# Project_Schem_v1.net
KiCad netlist of a schematic drawn in EAGLE
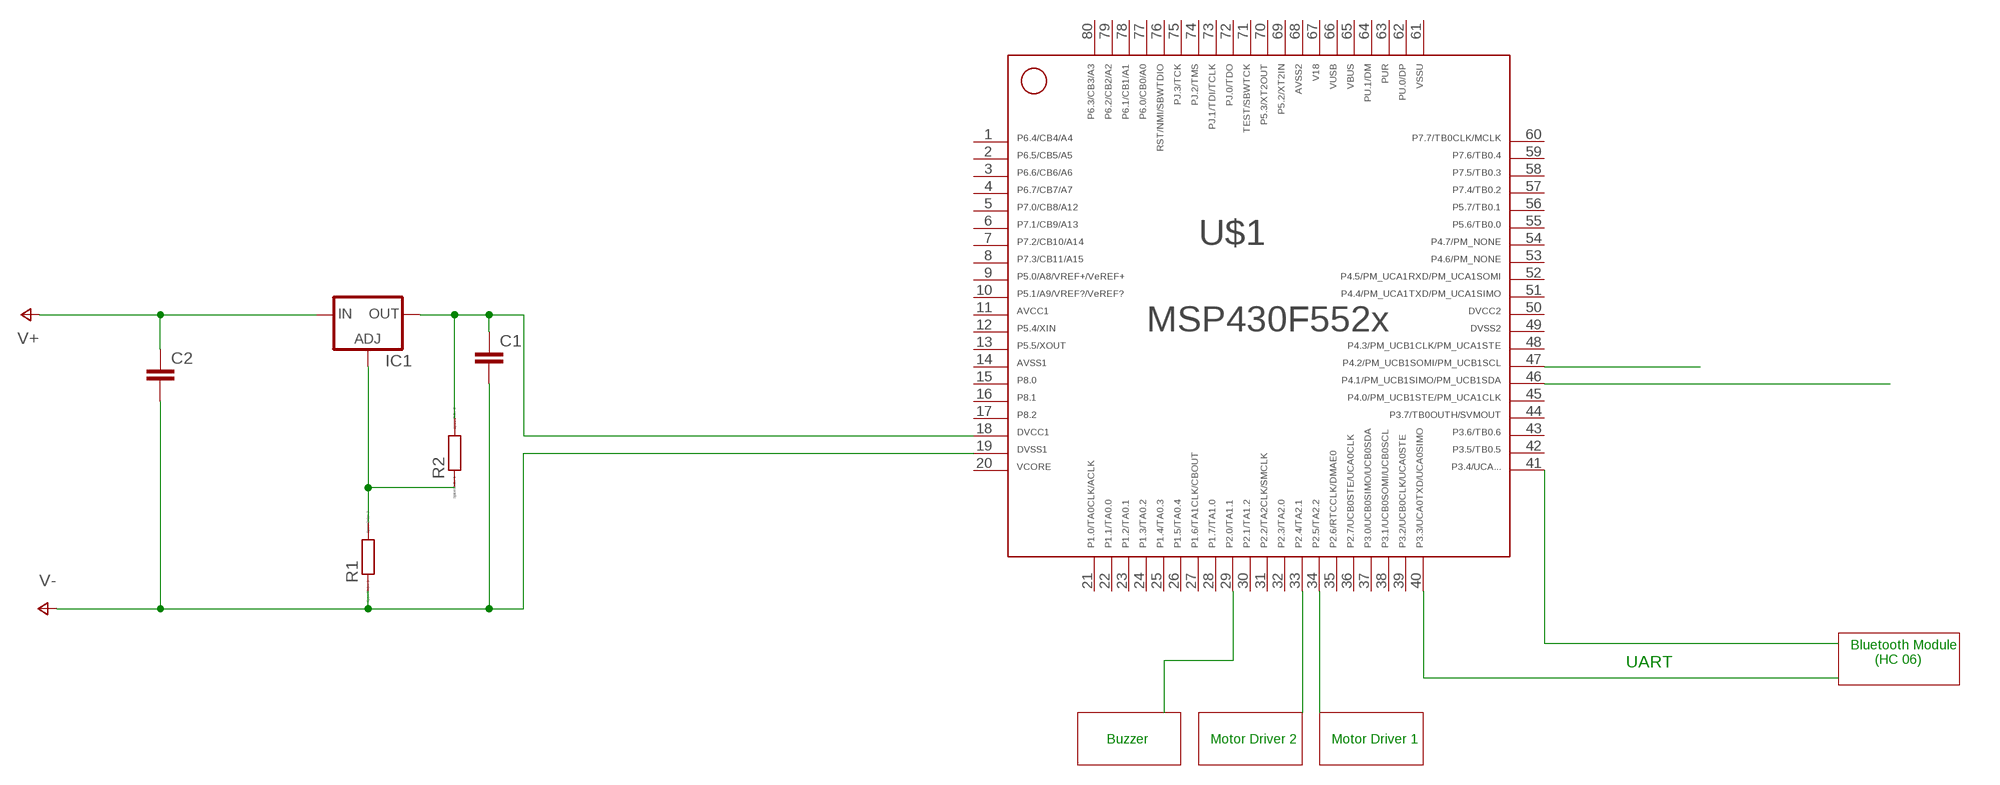
[diagram p0: schematic, sheet 1]

(export (version "E")
  (design (tool "Eeschema 10.0.6"))
  (components
    (comp (ref "C1")
      (value "C2.5/2")
      (footprint "eagle-import:C2.5-2")
      (libsource (lib "eagle-import") (part "C2.5/2"))
    )
    (comp (ref "C2")
      (value "C2.5/2")
      (footprint "eagle-import:C2.5-2")
      (libsource (lib "eagle-import") (part "C2.5/2"))
    )
    (comp (ref "IC1")
      (value "LM317TS")
      (footprint "eagle-import:317TS")
      (libsource (lib "eagle-import") (part "LM317TS"))
    )
    (comp (ref "R1")
      (value "R0204/7")
      (footprint "eagle-import:0204_7")
      (libsource (lib "eagle-import") (part "R0204/7"))
    )
    (comp (ref "R2")
      (value "R0204/7")
      (footprint "eagle-import:0204_7")
      (libsource (lib "eagle-import") (part "R0204/7"))
    )
    (comp (ref "U$1")
      (value "F552X---PN80")
      (footprint "eagle-import:PN80")
      (libsource (lib "eagle-import") (part "F552X---PN80"))
    )
  )
  (nets
    (net (code "1") (name "/11") (class "Default")
      (node (ref "U$1") (pin "11") (pinfunction "11_11") (pintype "power_in"))
    )
    (net (code "2") (name "/14") (class "Default")
      (node (ref "U$1") (pin "14") (pinfunction "14_14") (pintype "power_in"))
    )
    (net (code "3") (name "/20") (class "Default")
      (node (ref "U$1") (pin "20") (pinfunction "20_20") (pintype "power_in"))
    )
    (net (code "4") (name "/49") (class "Default")
      (node (ref "U$1") (pin "49") (pinfunction "49_49") (pintype "power_in"))
    )
    (net (code "5") (name "/50") (class "Default")
      (node (ref "U$1") (pin "50") (pinfunction "50_50") (pintype "power_in"))
    )
    (net (code "6") (name "/61") (class "Default")
      (node (ref "U$1") (pin "61") (pinfunction "61_61") (pintype "power_in"))
    )
    (net (code "7") (name "/65") (class "Default")
      (node (ref "U$1") (pin "65") (pinfunction "65_65") (pintype "power_in"))
    )
    (net (code "8") (name "/66") (class "Default")
      (node (ref "U$1") (pin "66") (pinfunction "66_66") (pintype "power_in"))
    )
    (net (code "9") (name "/67") (class "Default")
      (node (ref "U$1") (pin "67") (pinfunction "67_67") (pintype "power_in"))
    )
    (net (code "10") (name "/68") (class "Default")
      (node (ref "U$1") (pin "68") (pinfunction "68_68") (pintype "power_in"))
    )
    (net (code "11") (name "Net-(IC1-ADJ)") (class "Default")
      (node (ref "IC1") (pin "1") (pinfunction "ADJ_1") (pintype "input"))
      (node (ref "R1") (pin "2") (pinfunction "2_2") (pintype "passive"))
      (node (ref "R2") (pin "1") (pinfunction "1_1") (pintype "passive"))
    )
    (net (code "12") (name "Net-(IC1-OUT)") (class "Default")
      (node (ref "C1") (pin "1") (pinfunction "1_1") (pintype "passive"))
      (node (ref "IC1") (pin "2") (pinfunction "OUT_2") (pintype "passive"))
      (node (ref "R2") (pin "2") (pinfunction "2_2") (pintype "passive"))
      (node (ref "U$1") (pin "18") (pinfunction "18_18") (pintype "power_in"))
    )
    (net (code "13") (name "V+") (class "Default")
      (node (ref "C2") (pin "1") (pinfunction "1_1") (pintype "passive"))
      (node (ref "IC1") (pin "3") (pinfunction "IN_3") (pintype "input"))
    )
    (net (code "14") (name "V-") (class "Default")
      (node (ref "C1") (pin "2") (pinfunction "2_2") (pintype "passive"))
      (node (ref "C2") (pin "2") (pinfunction "2_2") (pintype "passive"))
      (node (ref "R1") (pin "1") (pinfunction "1_1") (pintype "passive"))
      (node (ref "U$1") (pin "19") (pinfunction "19_19") (pintype "power_in"))
    )
    (net (code "15") (name "unconnected-(U$1-Pad1)") (class "Default")
      (node (ref "U$1") (pin "1") (pinfunction "1_1") (pintype "bidirectional"))
    )
    (net (code "16") (name "unconnected-(U$1-Pad2)") (class "Default")
      (node (ref "U$1") (pin "2") (pinfunction "2_2") (pintype "bidirectional"))
    )
    (net (code "17") (name "unconnected-(U$1-Pad3)") (class "Default")
      (node (ref "U$1") (pin "3") (pinfunction "3_3") (pintype "bidirectional"))
    )
    (net (code "18") (name "unconnected-(U$1-Pad4)") (class "Default")
      (node (ref "U$1") (pin "4") (pinfunction "4_4") (pintype "bidirectional"))
    )
    (net (code "19") (name "unconnected-(U$1-Pad5)") (class "Default")
      (node (ref "U$1") (pin "5") (pinfunction "5_5") (pintype "bidirectional"))
    )
    (net (code "20") (name "unconnected-(U$1-Pad6)") (class "Default")
      (node (ref "U$1") (pin "6") (pinfunction "6_6") (pintype "bidirectional"))
    )
    (net (code "21") (name "unconnected-(U$1-Pad7)") (class "Default")
      (node (ref "U$1") (pin "7") (pinfunction "7_7") (pintype "bidirectional"))
    )
    (net (code "22") (name "unconnected-(U$1-Pad8)") (class "Default")
      (node (ref "U$1") (pin "8") (pinfunction "8_8") (pintype "bidirectional"))
    )
    (net (code "23") (name "unconnected-(U$1-Pad9)") (class "Default")
      (node (ref "U$1") (pin "9") (pinfunction "9_9") (pintype "bidirectional"))
    )
    (net (code "24") (name "unconnected-(U$1-Pad10)") (class "Default")
      (node (ref "U$1") (pin "10") (pinfunction "10_10") (pintype "bidirectional"))
    )
    (net (code "25") (name "unconnected-(U$1-Pad12)") (class "Default")
      (node (ref "U$1") (pin "12") (pinfunction "12_12") (pintype "bidirectional"))
    )
    (net (code "26") (name "unconnected-(U$1-Pad13)") (class "Default")
      (node (ref "U$1") (pin "13") (pinfunction "13_13") (pintype "bidirectional"))
    )
    (net (code "27") (name "unconnected-(U$1-Pad15)") (class "Default")
      (node (ref "U$1") (pin "15") (pinfunction "15_15") (pintype "bidirectional"))
    )
    (net (code "28") (name "unconnected-(U$1-Pad16)") (class "Default")
      (node (ref "U$1") (pin "16") (pinfunction "16_16") (pintype "bidirectional"))
    )
    (net (code "29") (name "unconnected-(U$1-Pad17)") (class "Default")
      (node (ref "U$1") (pin "17") (pinfunction "17_17") (pintype "bidirectional"))
    )
    (net (code "30") (name "unconnected-(U$1-Pad21)") (class "Default")
      (node (ref "U$1") (pin "21") (pinfunction "21_21") (pintype "bidirectional"))
    )
    (net (code "31") (name "unconnected-(U$1-Pad22)") (class "Default")
      (node (ref "U$1") (pin "22") (pinfunction "22_22") (pintype "bidirectional"))
    )
    (net (code "32") (name "unconnected-(U$1-Pad23)") (class "Default")
      (node (ref "U$1") (pin "23") (pinfunction "23_23") (pintype "bidirectional"))
    )
    (net (code "33") (name "unconnected-(U$1-Pad24)") (class "Default")
      (node (ref "U$1") (pin "24") (pinfunction "24_24") (pintype "bidirectional"))
    )
    (net (code "34") (name "unconnected-(U$1-Pad25)") (class "Default")
      (node (ref "U$1") (pin "25") (pinfunction "25_25") (pintype "bidirectional"))
    )
    (net (code "35") (name "unconnected-(U$1-Pad26)") (class "Default")
      (node (ref "U$1") (pin "26") (pinfunction "26_26") (pintype "bidirectional"))
    )
    (net (code "36") (name "unconnected-(U$1-Pad27)") (class "Default")
      (node (ref "U$1") (pin "27") (pinfunction "27_27") (pintype "bidirectional"))
    )
    (net (code "37") (name "unconnected-(U$1-Pad28)") (class "Default")
      (node (ref "U$1") (pin "28") (pinfunction "28_28") (pintype "bidirectional"))
    )
    (net (code "38") (name "unconnected-(U$1-Pad29)") (class "Default")
      (node (ref "U$1") (pin "29") (pinfunction "29_29") (pintype "bidirectional"))
    )
    (net (code "39") (name "unconnected-(U$1-Pad30)") (class "Default")
      (node (ref "U$1") (pin "30") (pinfunction "30_30") (pintype "bidirectional"))
    )
    (net (code "40") (name "unconnected-(U$1-Pad31)") (class "Default")
      (node (ref "U$1") (pin "31") (pinfunction "31_31") (pintype "bidirectional"))
    )
    (net (code "41") (name "unconnected-(U$1-Pad32)") (class "Default")
      (node (ref "U$1") (pin "32") (pinfunction "32_32") (pintype "bidirectional"))
    )
    (net (code "42") (name "unconnected-(U$1-Pad33)") (class "Default")
      (node (ref "U$1") (pin "33") (pinfunction "33_33") (pintype "bidirectional"))
    )
    (net (code "43") (name "unconnected-(U$1-Pad34)") (class "Default")
      (node (ref "U$1") (pin "34") (pinfunction "34_34") (pintype "bidirectional"))
    )
    (net (code "44") (name "unconnected-(U$1-Pad35)") (class "Default")
      (node (ref "U$1") (pin "35") (pinfunction "35_35") (pintype "bidirectional"))
    )
    (net (code "45") (name "unconnected-(U$1-Pad36)") (class "Default")
      (node (ref "U$1") (pin "36") (pinfunction "36_36") (pintype "bidirectional"))
    )
    (net (code "46") (name "unconnected-(U$1-Pad37)") (class "Default")
      (node (ref "U$1") (pin "37") (pinfunction "37_37") (pintype "bidirectional"))
    )
    (net (code "47") (name "unconnected-(U$1-Pad38)") (class "Default")
      (node (ref "U$1") (pin "38") (pinfunction "38_38") (pintype "bidirectional"))
    )
    (net (code "48") (name "unconnected-(U$1-Pad39)") (class "Default")
      (node (ref "U$1") (pin "39") (pinfunction "39_39") (pintype "bidirectional"))
    )
    (net (code "49") (name "unconnected-(U$1-Pad40)") (class "Default")
      (node (ref "U$1") (pin "40") (pinfunction "40_40") (pintype "bidirectional"))
    )
    (net (code "50") (name "unconnected-(U$1-Pad41)") (class "Default")
      (node (ref "U$1") (pin "41") (pinfunction "41_41") (pintype "bidirectional"))
    )
    (net (code "51") (name "unconnected-(U$1-Pad42)") (class "Default")
      (node (ref "U$1") (pin "42") (pinfunction "42_42") (pintype "bidirectional"))
    )
    (net (code "52") (name "unconnected-(U$1-Pad43)") (class "Default")
      (node (ref "U$1") (pin "43") (pinfunction "43_43") (pintype "bidirectional"))
    )
    (net (code "53") (name "unconnected-(U$1-Pad44)") (class "Default")
      (node (ref "U$1") (pin "44") (pinfunction "44_44") (pintype "bidirectional"))
    )
    (net (code "54") (name "unconnected-(U$1-Pad45)") (class "Default")
      (node (ref "U$1") (pin "45") (pinfunction "45_45") (pintype "bidirectional"))
    )
    (net (code "55") (name "unconnected-(U$1-Pad46)") (class "Default")
      (node (ref "U$1") (pin "46") (pinfunction "46_46") (pintype "bidirectional"))
    )
    (net (code "56") (name "unconnected-(U$1-Pad47)") (class "Default")
      (node (ref "U$1") (pin "47") (pinfunction "47_47") (pintype "bidirectional"))
    )
    (net (code "57") (name "unconnected-(U$1-Pad48)") (class "Default")
      (node (ref "U$1") (pin "48") (pinfunction "48_48") (pintype "bidirectional"))
    )
    (net (code "58") (name "unconnected-(U$1-Pad51)") (class "Default")
      (node (ref "U$1") (pin "51") (pinfunction "51_51") (pintype "bidirectional"))
    )
    (net (code "59") (name "unconnected-(U$1-Pad52)") (class "Default")
      (node (ref "U$1") (pin "52") (pinfunction "52_52") (pintype "bidirectional"))
    )
    (net (code "60") (name "unconnected-(U$1-Pad53)") (class "Default")
      (node (ref "U$1") (pin "53") (pinfunction "53_53") (pintype "bidirectional"))
    )
    (net (code "61") (name "unconnected-(U$1-Pad54)") (class "Default")
      (node (ref "U$1") (pin "54") (pinfunction "54_54") (pintype "bidirectional"))
    )
    (net (code "62") (name "unconnected-(U$1-Pad55)") (class "Default")
      (node (ref "U$1") (pin "55") (pinfunction "55_55") (pintype "bidirectional"))
    )
    (net (code "63") (name "unconnected-(U$1-Pad56)") (class "Default")
      (node (ref "U$1") (pin "56") (pinfunction "56_56") (pintype "bidirectional"))
    )
    (net (code "64") (name "unconnected-(U$1-Pad57)") (class "Default")
      (node (ref "U$1") (pin "57") (pinfunction "57_57") (pintype "bidirectional"))
    )
    (net (code "65") (name "unconnected-(U$1-Pad58)") (class "Default")
      (node (ref "U$1") (pin "58") (pinfunction "58_58") (pintype "bidirectional"))
    )
    (net (code "66") (name "unconnected-(U$1-Pad59)") (class "Default")
      (node (ref "U$1") (pin "59") (pinfunction "59_59") (pintype "bidirectional"))
    )
    (net (code "67") (name "unconnected-(U$1-Pad60)") (class "Default")
      (node (ref "U$1") (pin "60") (pinfunction "60_60") (pintype "bidirectional"))
    )
    (net (code "68") (name "unconnected-(U$1-Pad62)") (class "Default")
      (node (ref "U$1") (pin "62") (pinfunction "62_62") (pintype "bidirectional"))
    )
    (net (code "69") (name "unconnected-(U$1-Pad63)") (class "Default")
      (node (ref "U$1") (pin "63") (pinfunction "63_63") (pintype "bidirectional"))
    )
    (net (code "70") (name "unconnected-(U$1-Pad64)") (class "Default")
      (node (ref "U$1") (pin "64") (pinfunction "64_64") (pintype "bidirectional"))
    )
    (net (code "71") (name "unconnected-(U$1-Pad69)") (class "Default")
      (node (ref "U$1") (pin "69") (pinfunction "69_69") (pintype "bidirectional"))
    )
    (net (code "72") (name "unconnected-(U$1-Pad70)") (class "Default")
      (node (ref "U$1") (pin "70") (pinfunction "70_70") (pintype "bidirectional"))
    )
    (net (code "73") (name "unconnected-(U$1-Pad71)") (class "Default")
      (node (ref "U$1") (pin "71") (pinfunction "71_71") (pintype "input"))
    )
    (net (code "74") (name "unconnected-(U$1-Pad72)") (class "Default")
      (node (ref "U$1") (pin "72") (pinfunction "72_72") (pintype "bidirectional"))
    )
    (net (code "75") (name "unconnected-(U$1-Pad73)") (class "Default")
      (node (ref "U$1") (pin "73") (pinfunction "73_73") (pintype "bidirectional"))
    )
    (net (code "76") (name "unconnected-(U$1-Pad74)") (class "Default")
      (node (ref "U$1") (pin "74") (pinfunction "74_74") (pintype "bidirectional"))
    )
    (net (code "77") (name "unconnected-(U$1-Pad75)") (class "Default")
      (node (ref "U$1") (pin "75") (pinfunction "75_75") (pintype "bidirectional"))
    )
    (net (code "78") (name "unconnected-(U$1-Pad76)") (class "Default")
      (node (ref "U$1") (pin "76") (pinfunction "76_76") (pintype "bidirectional"))
    )
    (net (code "79") (name "unconnected-(U$1-Pad77)") (class "Default")
      (node (ref "U$1") (pin "77") (pinfunction "77_77") (pintype "bidirectional"))
    )
    (net (code "80") (name "unconnected-(U$1-Pad78)") (class "Default")
      (node (ref "U$1") (pin "78") (pinfunction "78_78") (pintype "bidirectional"))
    )
    (net (code "81") (name "unconnected-(U$1-Pad79)") (class "Default")
      (node (ref "U$1") (pin "79") (pinfunction "79_79") (pintype "bidirectional"))
    )
    (net (code "82") (name "unconnected-(U$1-Pad80)") (class "Default")
      (node (ref "U$1") (pin "80") (pinfunction "80_80") (pintype "bidirectional"))
    )
  )
)
